# esq.net
KiCad netlist of a schematic drawn in Altium Designer
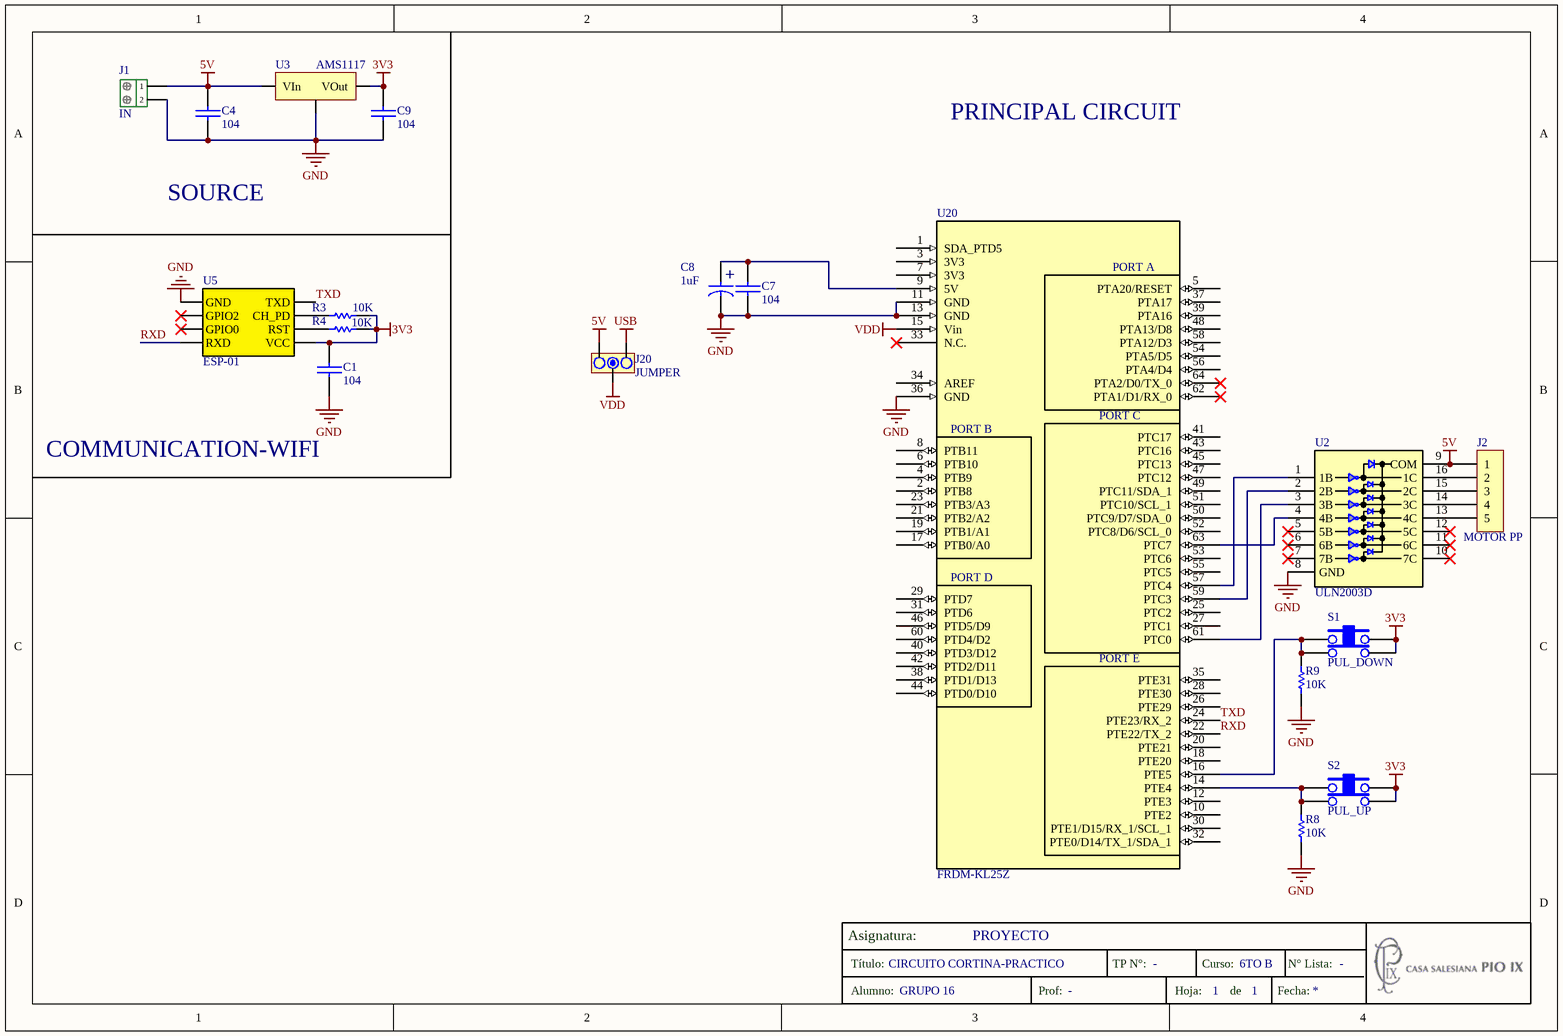
[diagram p0: esq.SchDoc]

(export (version "E")
  (design (tool "Eeschema 10.0.6"))
  (components
    (comp (ref "C1")
      (value "104")
      (footprint "0805")
      (description "cap")
      (fields (field (name "AUTOR") "Guido Spataro"))
      (libsource (lib "scdlib") (part "CAP"))
    )
    (comp (ref "C4")
      (value "104")
      (footprint "0805")
      (description "cap")
      (fields (field (name "AUTOR") "Guido Spataro"))
      (libsource (lib "Schlib1") (part "CAP"))
    )
    (comp (ref "C7")
      (value "104")
      (footprint "0805")
      (description "cap")
      (fields (field (name "AUTOR") "Guido Spataro"))
      (libsource (lib "scdlib") (part "CAP"))
    )
    (comp (ref "C8")
      (value "1uF")
      (footprint "CAP100RP")
      (description "Cap polarizado")
      (libsource (lib "scdlib") (part "CAPPOL"))
    )
    (comp (ref "C9")
      (value "104")
      (footprint "0805")
      (description "cap")
      (fields (field (name "AUTOR") "Guido Spataro"))
      (libsource (lib "scdlib") (part "CAP"))
    )
    (comp (ref "J1")
      (value "IN")
      (footprint "BORNERA2")
      (description "Bornera de 2 pines")
      (fields (field (name "AUTOR") "Guido Spataro"))
      (libsource (lib "scdlib") (part "Bornera_2"))
    )
    (comp (ref "J2") (value "MOTOR PP") (footprint "SIP5") (libsource (lib "scdlib") (part "CON5")))
    (comp (ref "J20") (value "JUMPER") (footprint "JUMPER3") (libsource (lib "scdlib") (part "JUMPER3")))
    (comp (ref "R3")
      (value "10K")
      (footprint "0805")
      (description "Resistencia")
      (fields (field (name "AUTOR") "Guido Spataro"))
      (libsource (lib "scdlib") (part "RES"))
    )
    (comp (ref "R4")
      (value "10K")
      (footprint "0805")
      (description "Resistencia")
      (fields (field (name "AUTOR") "Guido Spataro"))
      (libsource (lib "scdlib") (part "RES"))
    )
    (comp (ref "R8")
      (value "10K")
      (footprint "0805")
      (description "Resistencia")
      (fields (field (name "AUTOR") "Guido Spataro"))
      (libsource (lib "scdlib") (part "RES"))
    )
    (comp (ref "R9")
      (value "10K")
      (footprint "0805")
      (description "Resistencia")
      (fields (field (name "AUTOR") "Guido Spataro"))
      (libsource (lib "scdlib") (part "RES"))
    )
    (comp (ref "S1")
      (value "PUL_DOWN")
      (footprint "TACTSWITCH")
      (libsource (lib "scdlib") (part "TACT SWITCH"))
    )
    (comp (ref "S2")
      (value "PUL_UP")
      (footprint "TACTSWITCH")
      (libsource (lib "scdlib") (part "TACT SWITCH"))
    )
    (comp (ref "U2")
      (value "ULN2003D")
      (footprint "SOIC16")
      (description "Controlador de corriente")
      (fields (field (name "AUTOR") "MARTINEZ Agustin"))
      (libsource (lib "simbolo") (part "ULN2003D"))
    )
    (comp (ref "U3") (value "AMS1117") (footprint "AMS1117") (libsource (lib "scdlib") (part "AMS1117")))
    (comp (ref "U5") (value "ESP-01") (footprint "ESP-01") (libsource (lib "Schlib1") (part "ESP-01")))
    (comp (ref "U20")
      (value "FRDM-KL25Z")
      (footprint "MICRO")
      (fields (field (name "AUTOR") "Guido Spataro"))
      (libsource (lib "Schlib1") (part "FRDM-KL25Z"))
    )
  )
  (nets
    (net (code "1") (name "/RXD") (class "Default")
      (node (ref "U20") (pin "22") (pinfunction "PTE22/TX_2_22") (pintype "bidirectional"))
      (node (ref "U5") (pin "4") (pinfunction "RXD_4") (pintype "passive"))
    )
    (net (code "2") (name "/TXD") (class "Default")
      (node (ref "U20") (pin "24") (pinfunction "PTE23/RX_2_24") (pintype "bidirectional"))
      (node (ref "U5") (pin "5") (pinfunction "TXD_5") (pintype "passive"))
    )
    (net (code "3") (name "3V3") (class "Default")
      (node (ref "C1") (pin "2") (pinfunction "2_2") (pintype "passive"))
      (node (ref "C9") (pin "1") (pinfunction "1_1") (pintype "passive"))
      (node (ref "R3") (pin "1") (pinfunction "1_1") (pintype "passive"))
      (node (ref "R4") (pin "1") (pinfunction "1_1") (pintype "passive"))
      (node (ref "S1") (pin "3") (pinfunction "3_3") (pintype "passive"))
      (node (ref "S1") (pin "4") (pinfunction "4_4") (pintype "passive"))
      (node (ref "S2") (pin "3") (pinfunction "3_3") (pintype "passive"))
      (node (ref "S2") (pin "4") (pinfunction "4_4") (pintype "passive"))
      (node (ref "U3") (pin "3") (pinfunction "VOut_3") (pintype "passive"))
      (node (ref "U5") (pin "8") (pinfunction "VCC_8") (pintype "passive"))
    )
    (net (code "4") (name "5V") (class "Default")
      (node (ref "C4") (pin "1") (pinfunction "1_1") (pintype "passive"))
      (node (ref "J1") (pin "1") (pinfunction "1_1") (pintype "passive"))
      (node (ref "J2") (pin "1") (pinfunction "1_1") (pintype "passive"))
      (node (ref "J20") (pin "1") (pinfunction "1_1") (pintype "passive"))
      (node (ref "U2") (pin "9") (pinfunction "COM_9") (pintype "passive"))
      (node (ref "U3") (pin "1") (pinfunction "VIn_1") (pintype "passive"))
    )
    (net (code "5") (name "GND") (class "Default")
      (node (ref "C1") (pin "1") (pinfunction "1_1") (pintype "passive"))
      (node (ref "C4") (pin "2") (pinfunction "2_2") (pintype "passive"))
      (node (ref "C7") (pin "1") (pinfunction "1_1") (pintype "passive"))
      (node (ref "C8") (pin "2") (pinfunction "2_2") (pintype "passive"))
      (node (ref "C9") (pin "2") (pinfunction "2_2") (pintype "passive"))
      (node (ref "J1") (pin "2") (pinfunction "2_2") (pintype "passive"))
      (node (ref "R8") (pin "1") (pinfunction "1_1") (pintype "passive"))
      (node (ref "R9") (pin "1") (pinfunction "1_1") (pintype "passive"))
      (node (ref "U2") (pin "8") (pinfunction "GND_8") (pintype "passive"))
      (node (ref "U20") (pin "11") (pinfunction "GND_11") (pintype "input"))
      (node (ref "U20") (pin "13") (pinfunction "GND_13") (pintype "input"))
      (node (ref "U20") (pin "36") (pinfunction "GND_36") (pintype "input"))
      (node (ref "U3") (pin "2") (pinfunction "GND_2") (pintype "passive"))
      (node (ref "U5") (pin "1") (pinfunction "GND_1") (pintype "passive"))
    )
    (net (code "6") (name "Net-(U2-1B)") (class "Default")
      (node (ref "U2") (pin "1") (pinfunction "1B_1") (pintype "passive"))
      (node (ref "U20") (pin "57") (pinfunction "PTC4_57") (pintype "bidirectional"))
    )
    (net (code "7") (name "Net-(U2-1C)") (class "Default")
      (node (ref "J2") (pin "2") (pinfunction "2_2") (pintype "passive"))
      (node (ref "U2") (pin "16") (pinfunction "1C_16") (pintype "passive"))
    )
    (net (code "8") (name "Net-(U2-2B)") (class "Default")
      (node (ref "U2") (pin "2") (pinfunction "2B_2") (pintype "passive"))
      (node (ref "U20") (pin "59") (pinfunction "PTC3_59") (pintype "bidirectional"))
    )
    (net (code "9") (name "Net-(U2-2C)") (class "Default")
      (node (ref "J2") (pin "3") (pinfunction "3_3") (pintype "passive"))
      (node (ref "U2") (pin "15") (pinfunction "2C_15") (pintype "passive"))
    )
    (net (code "10") (name "Net-(U2-3B)") (class "Default")
      (node (ref "U2") (pin "3") (pinfunction "3B_3") (pintype "passive"))
      (node (ref "U20") (pin "61") (pinfunction "PTC0_61") (pintype "bidirectional"))
    )
    (net (code "11") (name "Net-(U2-3C)") (class "Default")
      (node (ref "J2") (pin "4") (pinfunction "4_4") (pintype "passive"))
      (node (ref "U2") (pin "14") (pinfunction "3C_14") (pintype "passive"))
    )
    (net (code "12") (name "Net-(U2-4B)") (class "Default")
      (node (ref "U2") (pin "4") (pinfunction "4B_4") (pintype "passive"))
      (node (ref "U20") (pin "63") (pinfunction "PTC7_63") (pintype "bidirectional"))
    )
    (net (code "13") (name "Net-(U2-4C)") (class "Default")
      (node (ref "J2") (pin "5") (pinfunction "5_5") (pintype "passive"))
      (node (ref "U2") (pin "13") (pinfunction "4C_13") (pintype "passive"))
    )
    (net (code "14") (name "Net-(U5-CH_PD)") (class "Default")
      (node (ref "R3") (pin "2") (pinfunction "2_2") (pintype "passive"))
      (node (ref "U5") (pin "6") (pinfunction "CH_PD_6") (pintype "passive"))
    )
    (net (code "15") (name "Net-(U5-RST)") (class "Default")
      (node (ref "R4") (pin "2") (pinfunction "2_2") (pintype "passive"))
      (node (ref "U5") (pin "7") (pinfunction "RST_7") (pintype "passive"))
    )
    (net (code "16") (name "Net-(U20-5V)") (class "Default")
      (node (ref "C7") (pin "2") (pinfunction "2_2") (pintype "passive"))
      (node (ref "C8") (pin "1") (pinfunction "1_1") (pintype "passive"))
      (node (ref "U20") (pin "9") (pinfunction "5V_9") (pintype "input"))
    )
    (net (code "17") (name "Net-(U20-PTE4)") (class "Default")
      (node (ref "R8") (pin "2") (pinfunction "2_2") (pintype "passive"))
      (node (ref "S2") (pin "1") (pinfunction "1_1") (pintype "passive"))
      (node (ref "S2") (pin "2") (pinfunction "2_2") (pintype "passive"))
      (node (ref "U20") (pin "14") (pinfunction "PTE4_14") (pintype "bidirectional"))
    )
    (net (code "18") (name "Net-(U20-PTE5)") (class "Default")
      (node (ref "R9") (pin "2") (pinfunction "2_2") (pintype "passive"))
      (node (ref "S1") (pin "1") (pinfunction "1_1") (pintype "passive"))
      (node (ref "S1") (pin "2") (pinfunction "2_2") (pintype "passive"))
      (node (ref "U20") (pin "16") (pinfunction "PTE5_16") (pintype "bidirectional"))
    )
    (net (code "19") (name "USB") (class "Default")
      (node (ref "J20") (pin "3") (pinfunction "3_3") (pintype "passive"))
    )
    (net (code "20") (name "VDD") (class "Default")
      (node (ref "J20") (pin "2") (pinfunction "2_2") (pintype "passive"))
      (node (ref "U20") (pin "15") (pinfunction "Vin_15") (pintype "input"))
    )
    (net (code "21") (name "unconnected-(U2-5B-Pad5)") (class "Default")
      (node (ref "U2") (pin "5") (pinfunction "5B_5") (pintype "passive+no_connect"))
    )
    (net (code "22") (name "unconnected-(U2-5C-Pad12)") (class "Default")
      (node (ref "U2") (pin "12") (pinfunction "5C_12") (pintype "passive+no_connect"))
    )
    (net (code "23") (name "unconnected-(U2-6B-Pad6)") (class "Default")
      (node (ref "U2") (pin "6") (pinfunction "6B_6") (pintype "passive+no_connect"))
    )
    (net (code "24") (name "unconnected-(U2-6C-Pad11)") (class "Default")
      (node (ref "U2") (pin "11") (pinfunction "6C_11") (pintype "passive+no_connect"))
    )
    (net (code "25") (name "unconnected-(U2-7B-Pad7)") (class "Default")
      (node (ref "U2") (pin "7") (pinfunction "7B_7") (pintype "passive+no_connect"))
    )
    (net (code "26") (name "unconnected-(U2-7C-Pad10)") (class "Default")
      (node (ref "U2") (pin "10") (pinfunction "7C_10") (pintype "passive+no_connect"))
    )
    (net (code "27") (name "unconnected-(U5-GPIO0-Pad3)") (class "Default")
      (node (ref "U5") (pin "3") (pinfunction "GPIO0_3") (pintype "passive+no_connect"))
    )
    (net (code "28") (name "unconnected-(U5-GPIO2-Pad2)") (class "Default")
      (node (ref "U5") (pin "2") (pinfunction "GPIO2_2") (pintype "passive+no_connect"))
    )
    (net (code "29") (name "unconnected-(U20-3V3-Pad3)") (class "Default")
      (node (ref "U20") (pin "3") (pinfunction "3V3_3") (pintype "input"))
    )
    (net (code "30") (name "unconnected-(U20-3V3-Pad7)") (class "Default")
      (node (ref "U20") (pin "7") (pinfunction "3V3_7") (pintype "input"))
    )
    (net (code "31") (name "unconnected-(U20-AREF-Pad34)") (class "Default")
      (node (ref "U20") (pin "34") (pinfunction "AREF_34") (pintype "input"))
    )
    (net (code "32") (name "unconnected-(U20-N.C.-Pad33)") (class "Default")
      (node (ref "U20") (pin "33") (pinfunction "N.C._33") (pintype "open_emitter+no_connect"))
    )
    (net (code "33") (name "unconnected-(U20-PTA1{slash}D1{slash}RX_0-Pad62)") (class "Default")
      (node (ref "U20") (pin "62") (pinfunction "PTA1/D1/RX_0_62") (pintype "bidirectional+no_connect"))
    )
    (net (code "34") (name "unconnected-(U20-PTA2{slash}D0{slash}TX_0-Pad64)") (class "Default")
      (node (ref "U20") (pin "64") (pinfunction "PTA2/D0/TX_0_64") (pintype "bidirectional+no_connect"))
    )
    (net (code "35") (name "unconnected-(U20-PTA4{slash}D4-Pad56)") (class "Default")
      (node (ref "U20") (pin "56") (pinfunction "PTA4/D4_56") (pintype "bidirectional"))
    )
    (net (code "36") (name "unconnected-(U20-PTA5{slash}D5-Pad54)") (class "Default")
      (node (ref "U20") (pin "54") (pinfunction "PTA5/D5_54") (pintype "bidirectional"))
    )
    (net (code "37") (name "unconnected-(U20-PTA12{slash}D3-Pad58)") (class "Default")
      (node (ref "U20") (pin "58") (pinfunction "PTA12/D3_58") (pintype "bidirectional"))
    )
    (net (code "38") (name "unconnected-(U20-PTA13{slash}D8-Pad48)") (class "Default")
      (node (ref "U20") (pin "48") (pinfunction "PTA13/D8_48") (pintype "bidirectional"))
    )
    (net (code "39") (name "unconnected-(U20-PTA16-Pad39)") (class "Default")
      (node (ref "U20") (pin "39") (pinfunction "PTA16_39") (pintype "bidirectional"))
    )
    (net (code "40") (name "unconnected-(U20-PTA17-Pad37)") (class "Default")
      (node (ref "U20") (pin "37") (pinfunction "PTA17_37") (pintype "bidirectional"))
    )
    (net (code "41") (name "unconnected-(U20-PTA20{slash}RESET-Pad5)") (class "Default")
      (node (ref "U20") (pin "5") (pinfunction "PTA20/RESET_5") (pintype "bidirectional"))
    )
    (net (code "42") (name "unconnected-(U20-PTB0{slash}A0-Pad17)") (class "Default")
      (node (ref "U20") (pin "17") (pinfunction "PTB0/A0_17") (pintype "bidirectional"))
    )
    (net (code "43") (name "unconnected-(U20-PTB1{slash}A1-Pad19)") (class "Default")
      (node (ref "U20") (pin "19") (pinfunction "PTB1/A1_19") (pintype "bidirectional"))
    )
    (net (code "44") (name "unconnected-(U20-PTB2{slash}A2-Pad21)") (class "Default")
      (node (ref "U20") (pin "21") (pinfunction "PTB2/A2_21") (pintype "bidirectional"))
    )
    (net (code "45") (name "unconnected-(U20-PTB3{slash}A3-Pad23)") (class "Default")
      (node (ref "U20") (pin "23") (pinfunction "PTB3/A3_23") (pintype "bidirectional"))
    )
    (net (code "46") (name "unconnected-(U20-PTB8-Pad2)") (class "Default")
      (node (ref "U20") (pin "2") (pinfunction "PTB8_2") (pintype "bidirectional"))
    )
    (net (code "47") (name "unconnected-(U20-PTB9-Pad4)") (class "Default")
      (node (ref "U20") (pin "4") (pinfunction "PTB9_4") (pintype "bidirectional"))
    )
    (net (code "48") (name "unconnected-(U20-PTB10-Pad6)") (class "Default")
      (node (ref "U20") (pin "6") (pinfunction "PTB10_6") (pintype "bidirectional"))
    )
    (net (code "49") (name "unconnected-(U20-PTB11-Pad8)") (class "Default")
      (node (ref "U20") (pin "8") (pinfunction "PTB11_8") (pintype "bidirectional"))
    )
    (net (code "50") (name "unconnected-(U20-PTC1-Pad27)") (class "Default")
      (node (ref "U20") (pin "27") (pinfunction "PTC1_27") (pintype "bidirectional"))
    )
    (net (code "51") (name "unconnected-(U20-PTC2-Pad25)") (class "Default")
      (node (ref "U20") (pin "25") (pinfunction "PTC2_25") (pintype "bidirectional"))
    )
    (net (code "52") (name "unconnected-(U20-PTC5-Pad55)") (class "Default")
      (node (ref "U20") (pin "55") (pinfunction "PTC5_55") (pintype "bidirectional"))
    )
    (net (code "53") (name "unconnected-(U20-PTC6-Pad53)") (class "Default")
      (node (ref "U20") (pin "53") (pinfunction "PTC6_53") (pintype "bidirectional"))
    )
    (net (code "54") (name "unconnected-(U20-PTC8{slash}D6{slash}SCL_0-Pad52)") (class "Default")
      (node (ref "U20") (pin "52") (pinfunction "PTC8/D6/SCL_0_52") (pintype "bidirectional"))
    )
    (net (code "55") (name "unconnected-(U20-PTC9{slash}D7{slash}SDA_0-Pad50)") (class "Default")
      (node (ref "U20") (pin "50") (pinfunction "PTC9/D7/SDA_0_50") (pintype "bidirectional"))
    )
    (net (code "56") (name "unconnected-(U20-PTC10{slash}SCL_1-Pad51)") (class "Default")
      (node (ref "U20") (pin "51") (pinfunction "PTC10/SCL_1_51") (pintype "bidirectional"))
    )
    (net (code "57") (name "unconnected-(U20-PTC11{slash}SDA_1-Pad49)") (class "Default")
      (node (ref "U20") (pin "49") (pinfunction "PTC11/SDA_1_49") (pintype "bidirectional"))
    )
    (net (code "58") (name "unconnected-(U20-PTC12-Pad47)") (class "Default")
      (node (ref "U20") (pin "47") (pinfunction "PTC12_47") (pintype "bidirectional"))
    )
    (net (code "59") (name "unconnected-(U20-PTC13-Pad45)") (class "Default")
      (node (ref "U20") (pin "45") (pinfunction "PTC13_45") (pintype "bidirectional"))
    )
    (net (code "60") (name "unconnected-(U20-PTC16-Pad43)") (class "Default")
      (node (ref "U20") (pin "43") (pinfunction "PTC16_43") (pintype "bidirectional"))
    )
    (net (code "61") (name "unconnected-(U20-PTC17-Pad41)") (class "Default")
      (node (ref "U20") (pin "41") (pinfunction "PTC17_41") (pintype "bidirectional"))
    )
    (net (code "62") (name "unconnected-(U20-PTD0{slash}D10-Pad44)") (class "Default")
      (node (ref "U20") (pin "44") (pinfunction "PTD0/D10_44") (pintype "bidirectional"))
    )
    (net (code "63") (name "unconnected-(U20-PTD1{slash}D13-Pad38)") (class "Default")
      (node (ref "U20") (pin "38") (pinfunction "PTD1/D13_38") (pintype "bidirectional"))
    )
    (net (code "64") (name "unconnected-(U20-PTD2{slash}D11-Pad42)") (class "Default")
      (node (ref "U20") (pin "42") (pinfunction "PTD2/D11_42") (pintype "bidirectional"))
    )
    (net (code "65") (name "unconnected-(U20-PTD3{slash}D12-Pad40)") (class "Default")
      (node (ref "U20") (pin "40") (pinfunction "PTD3/D12_40") (pintype "bidirectional"))
    )
    (net (code "66") (name "unconnected-(U20-PTD4{slash}D2-Pad60)") (class "Default")
      (node (ref "U20") (pin "60") (pinfunction "PTD4/D2_60") (pintype "bidirectional"))
    )
    (net (code "67") (name "unconnected-(U20-PTD5{slash}D9-Pad46)") (class "Default")
      (node (ref "U20") (pin "46") (pinfunction "PTD5/D9_46") (pintype "bidirectional"))
    )
    (net (code "68") (name "unconnected-(U20-PTD6-Pad31)") (class "Default")
      (node (ref "U20") (pin "31") (pinfunction "PTD6_31") (pintype "bidirectional"))
    )
    (net (code "69") (name "unconnected-(U20-PTD7-Pad29)") (class "Default")
      (node (ref "U20") (pin "29") (pinfunction "PTD7_29") (pintype "bidirectional"))
    )
    (net (code "70") (name "unconnected-(U20-PTE0{slash}D14{slash}TX_1{slash}SDA_1-Pad32)") (class "Default")
      (node (ref "U20") (pin "32") (pinfunction "PTE0/D14/TX_1/SDA_1_32") (pintype "bidirectional"))
    )
    (net (code "71") (name "unconnected-(U20-PTE1{slash}D15{slash}RX_1{slash}SCL_1-Pad30)") (class "Default")
      (node (ref "U20") (pin "30") (pinfunction "PTE1/D15/RX_1/SCL_1_30") (pintype "bidirectional"))
    )
    (net (code "72") (name "unconnected-(U20-PTE2-Pad10)") (class "Default")
      (node (ref "U20") (pin "10") (pinfunction "PTE2_10") (pintype "bidirectional"))
    )
    (net (code "73") (name "unconnected-(U20-PTE3-Pad12)") (class "Default")
      (node (ref "U20") (pin "12") (pinfunction "PTE3_12") (pintype "bidirectional"))
    )
    (net (code "74") (name "unconnected-(U20-PTE20-Pad18)") (class "Default")
      (node (ref "U20") (pin "18") (pinfunction "PTE20_18") (pintype "bidirectional"))
    )
    (net (code "75") (name "unconnected-(U20-PTE21-Pad20)") (class "Default")
      (node (ref "U20") (pin "20") (pinfunction "PTE21_20") (pintype "bidirectional"))
    )
    (net (code "76") (name "unconnected-(U20-PTE29-Pad26)") (class "Default")
      (node (ref "U20") (pin "26") (pinfunction "PTE29_26") (pintype "bidirectional"))
    )
    (net (code "77") (name "unconnected-(U20-PTE30-Pad28)") (class "Default")
      (node (ref "U20") (pin "28") (pinfunction "PTE30_28") (pintype "bidirectional"))
    )
    (net (code "78") (name "unconnected-(U20-PTE31-Pad35)") (class "Default")
      (node (ref "U20") (pin "35") (pinfunction "PTE31_35") (pintype "bidirectional"))
    )
    (net (code "79") (name "unconnected-(U20-SDA_PTD5-Pad1)") (class "Default")
      (node (ref "U20") (pin "1") (pinfunction "SDA_PTD5_1") (pintype "input"))
    )
  )
)
